# Power_Distribution.net
KiCad netlist of a schematic drawn in EAGLE
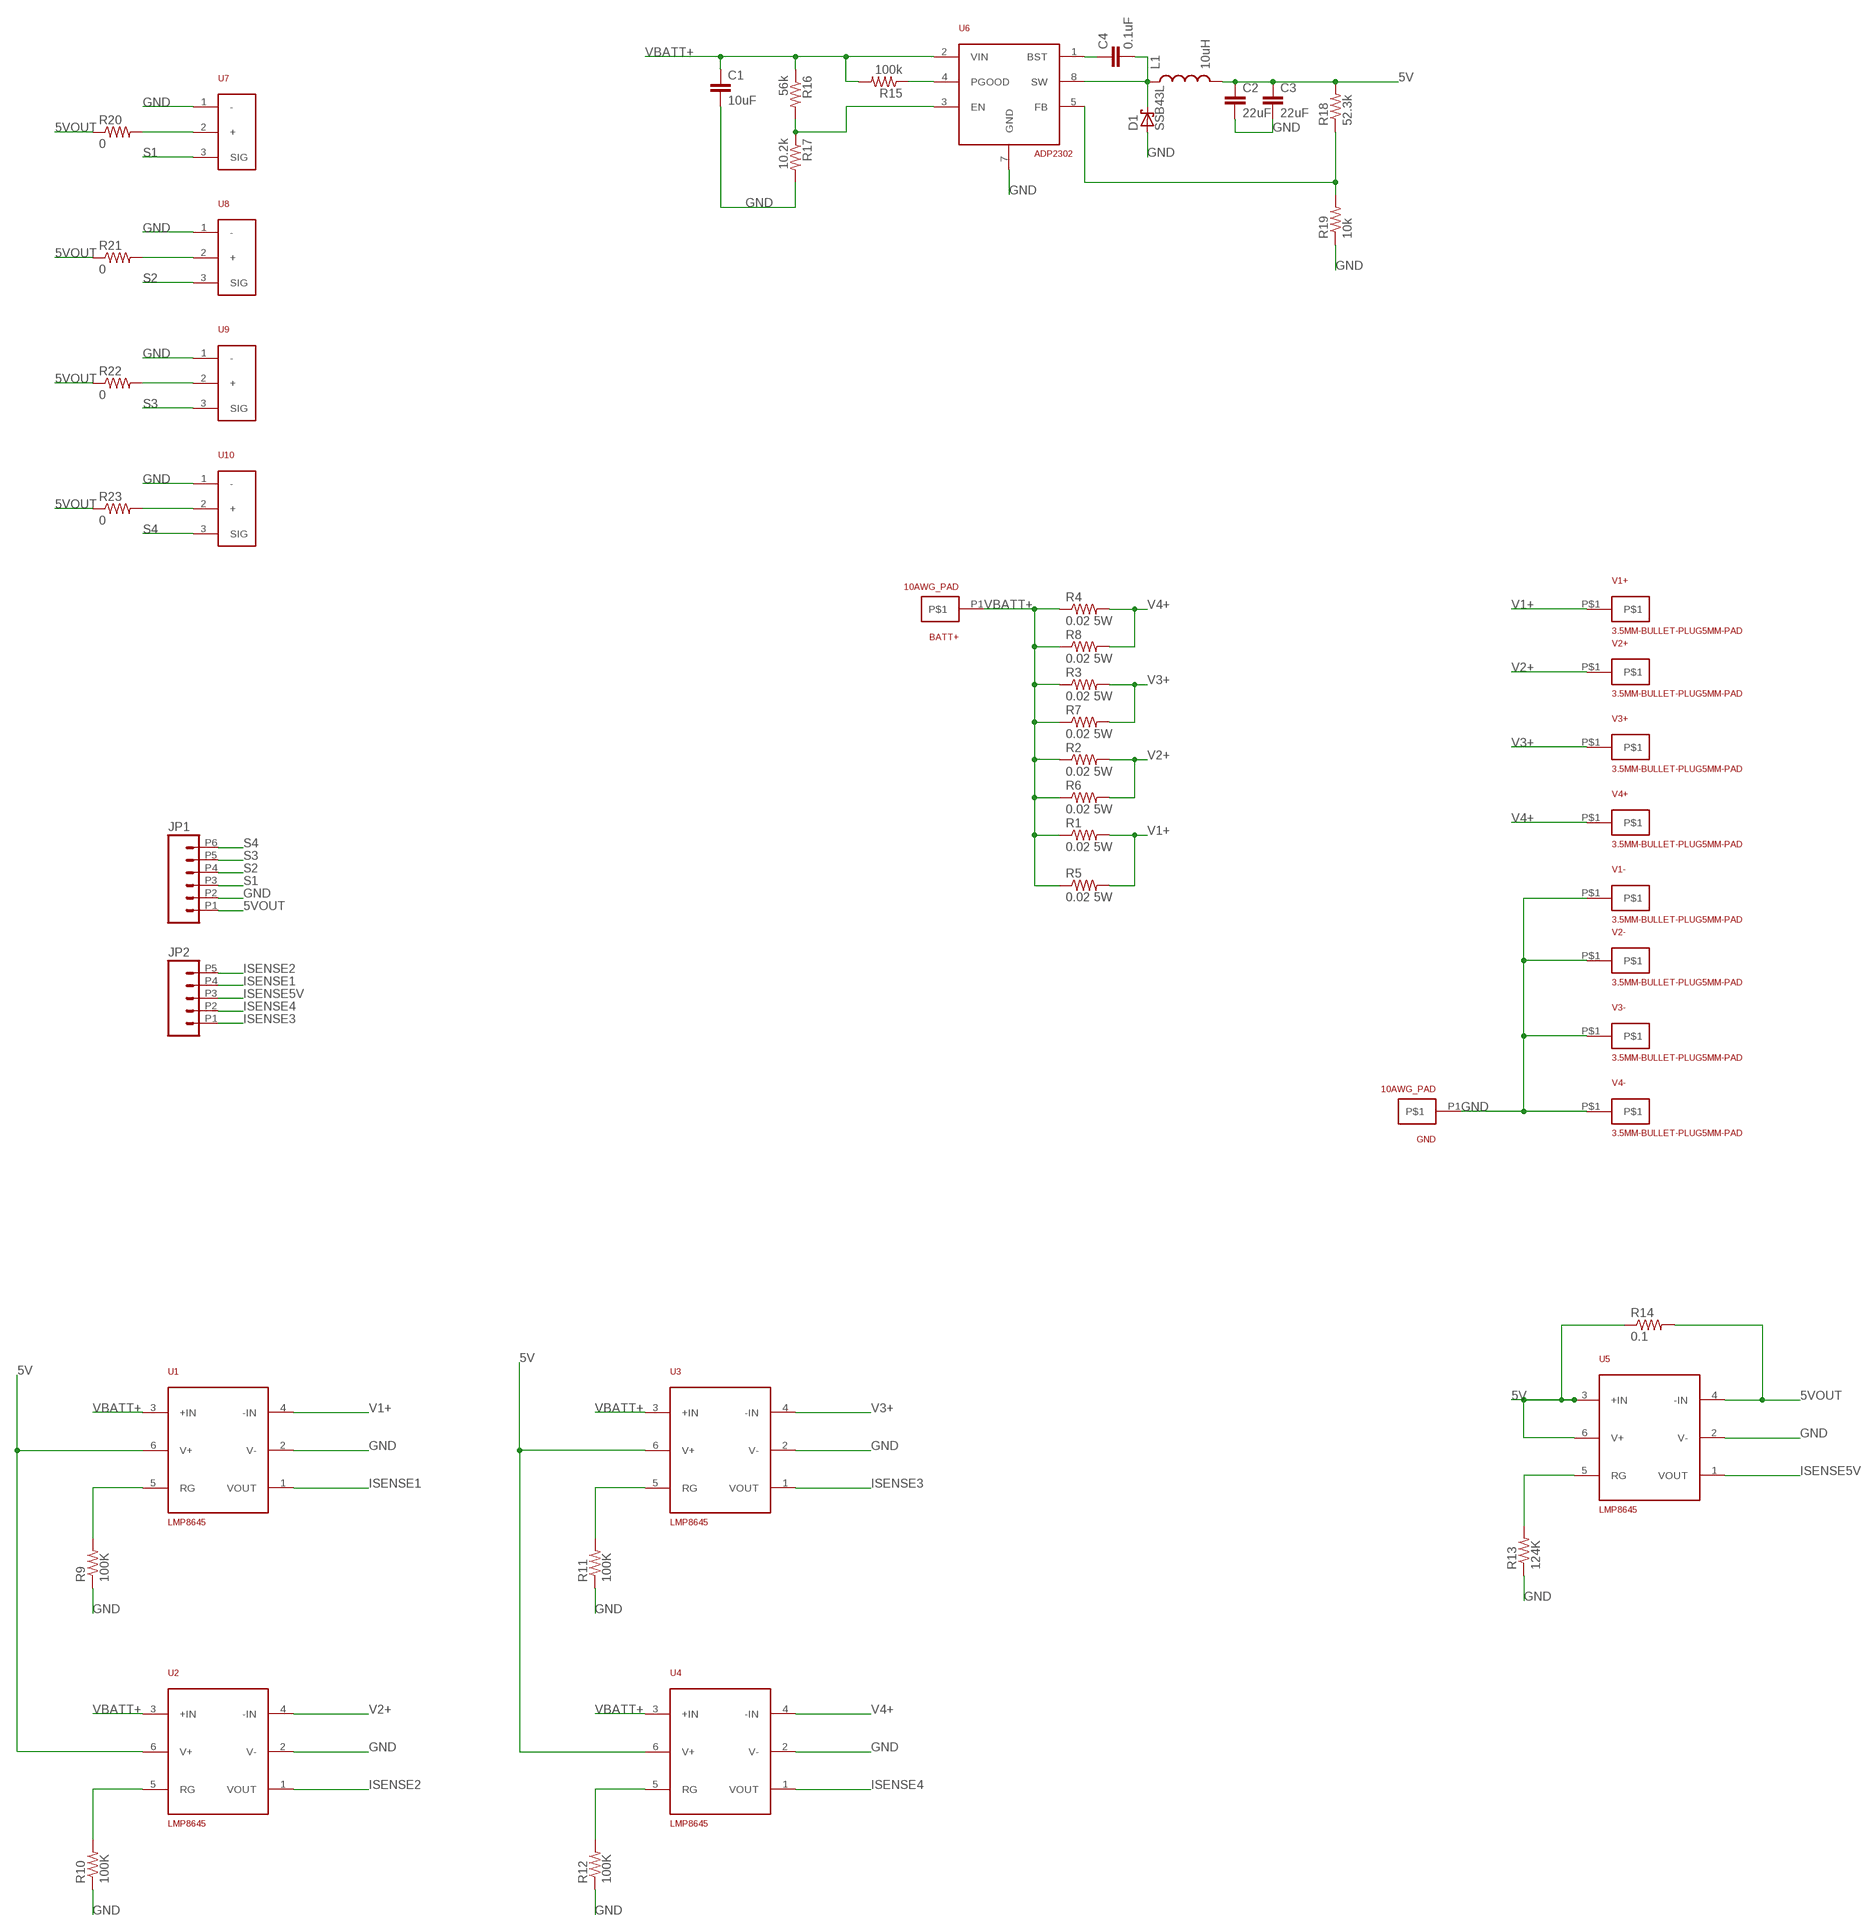
[diagram p0: schematic, sheet 1]

(export (version "E")
  (design (tool "Eeschema 10.0.6"))
  (components
    (comp (ref "BATT+")
      (value "10AWG_PAD")
      (footprint "eagle-import:10AWG_SOLDERPAD")
      (libsource (lib "eagle-import") (part "10AWG_PAD"))
    )
    (comp (ref "C1")
      (value "10uF")
      (footprint "eagle-import:0603-CAP")
      (libsource (lib "eagle-import") (part "CAP0603-CAP"))
    )
    (comp (ref "C2")
      (value "22uF")
      (footprint "eagle-import:0603-CAP")
      (libsource (lib "eagle-import") (part "CAP0603-CAP"))
    )
    (comp (ref "C3")
      (value "22uF")
      (footprint "eagle-import:0603-CAP")
      (libsource (lib "eagle-import") (part "CAP0603-CAP"))
    )
    (comp (ref "C4")
      (value "0.1uF")
      (footprint "eagle-import:0603-CAP")
      (libsource (lib "eagle-import") (part "CAP0603-CAP"))
    )
    (comp (ref "D1")
      (value "SSB43L")
      (footprint "eagle-import:SMB")
      (libsource (lib "eagle-import") (part "SCHOTTKY-DIODESMD"))
    )
    (comp (ref "GND")
      (value "10AWG_PAD")
      (footprint "eagle-import:10AWG_SOLDERPAD")
      (libsource (lib "eagle-import") (part "10AWG_PAD"))
    )
    (comp (ref "JP1")
      (value "M06DF13")
      (footprint "eagle-import:DF13A-6P-1.25H")
      (libsource (lib "eagle-import") (part "M06DF13"))
    )
    (comp (ref "JP2")
      (value "M05DF13")
      (footprint "eagle-import:DF13A-5P-1.25H")
      (libsource (lib "eagle-import") (part "M05DF13"))
    )
    (comp (ref "L1")
      (value "10uH")
      (footprint "eagle-import:0603")
      (libsource (lib "eagle-import") (part "INDUCTOR0603"))
    )
    (comp (ref "R1")
      (value "0.02 5W")
      (footprint "eagle-import:R2512")
      (libsource (lib "eagle-import") (part "RESISTOR2512"))
    )
    (comp (ref "R2")
      (value "0.02 5W")
      (footprint "eagle-import:R2512")
      (libsource (lib "eagle-import") (part "RESISTOR2512"))
    )
    (comp (ref "R3")
      (value "0.02 5W")
      (footprint "eagle-import:R2512")
      (libsource (lib "eagle-import") (part "RESISTOR2512"))
    )
    (comp (ref "R4")
      (value "0.02 5W")
      (footprint "eagle-import:R2512")
      (libsource (lib "eagle-import") (part "RESISTOR2512"))
    )
    (comp (ref "R5")
      (value "0.02 5W")
      (footprint "eagle-import:R2512")
      (libsource (lib "eagle-import") (part "RESISTOR2512"))
    )
    (comp (ref "R6")
      (value "0.02 5W")
      (footprint "eagle-import:R2512")
      (libsource (lib "eagle-import") (part "RESISTOR2512"))
    )
    (comp (ref "R7")
      (value "0.02 5W")
      (footprint "eagle-import:R2512")
      (libsource (lib "eagle-import") (part "RESISTOR2512"))
    )
    (comp (ref "R8")
      (value "0.02 5W")
      (footprint "eagle-import:R2512")
      (libsource (lib "eagle-import") (part "RESISTOR2512"))
    )
    (comp (ref "R9")
      (value "100K")
      (footprint "eagle-import:0603-RES")
      (libsource (lib "eagle-import") (part "RESISTOR0603-RES"))
    )
    (comp (ref "R10")
      (value "100K")
      (footprint "eagle-import:0603-RES")
      (libsource (lib "eagle-import") (part "RESISTOR0603-RES"))
    )
    (comp (ref "R11")
      (value "100K")
      (footprint "eagle-import:0603-RES")
      (libsource (lib "eagle-import") (part "RESISTOR0603-RES"))
    )
    (comp (ref "R12")
      (value "100K")
      (footprint "eagle-import:0603-RES")
      (libsource (lib "eagle-import") (part "RESISTOR0603-RES"))
    )
    (comp (ref "R13")
      (value "124K")
      (footprint "eagle-import:0603-RES")
      (libsource (lib "eagle-import") (part "RESISTOR0603-RES"))
    )
    (comp (ref "R14")
      (value "0.1")
      (footprint "eagle-import:0603-RES")
      (libsource (lib "eagle-import") (part "RESISTOR0603-RES"))
    )
    (comp (ref "R15")
      (value "100k")
      (footprint "eagle-import:0603-RES")
      (libsource (lib "eagle-import") (part "RESISTOR0603-RES"))
    )
    (comp (ref "R16")
      (value "56k")
      (footprint "eagle-import:0603-RES")
      (libsource (lib "eagle-import") (part "RESISTOR0603-RES"))
    )
    (comp (ref "R17")
      (value "10.2k")
      (footprint "eagle-import:0603-RES")
      (libsource (lib "eagle-import") (part "RESISTOR0603-RES"))
    )
    (comp (ref "R18")
      (value "52.3k")
      (footprint "eagle-import:0603-RES")
      (libsource (lib "eagle-import") (part "RESISTOR0603-RES"))
    )
    (comp (ref "R19")
      (value "10k")
      (footprint "eagle-import:0603-RES")
      (libsource (lib "eagle-import") (part "RESISTOR0603-RES"))
    )
    (comp (ref "R20")
      (value "0")
      (footprint "eagle-import:0603-RES")
      (libsource (lib "eagle-import") (part "RESISTOR0603-RES"))
    )
    (comp (ref "R21")
      (value "0")
      (footprint "eagle-import:0603-RES")
      (libsource (lib "eagle-import") (part "RESISTOR0603-RES"))
    )
    (comp (ref "R22")
      (value "0")
      (footprint "eagle-import:0603-RES")
      (libsource (lib "eagle-import") (part "RESISTOR0603-RES"))
    )
    (comp (ref "R23")
      (value "0")
      (footprint "eagle-import:0603-RES")
      (libsource (lib "eagle-import") (part "RESISTOR0603-RES"))
    )
    (comp (ref "U1")
      (value "LMP8645")
      (footprint "eagle-import:SOT23-6")
      (libsource (lib "eagle-import") (part "LMP8645"))
    )
    (comp (ref "U2")
      (value "LMP8645")
      (footprint "eagle-import:SOT23-6")
      (libsource (lib "eagle-import") (part "LMP8645"))
    )
    (comp (ref "U3")
      (value "LMP8645")
      (footprint "eagle-import:SOT23-6")
      (libsource (lib "eagle-import") (part "LMP8645"))
    )
    (comp (ref "U4")
      (value "LMP8645")
      (footprint "eagle-import:SOT23-6")
      (libsource (lib "eagle-import") (part "LMP8645"))
    )
    (comp (ref "U5")
      (value "LMP8645")
      (footprint "eagle-import:SOT23-6")
      (libsource (lib "eagle-import") (part "LMP8645"))
    )
    (comp (ref "U6")
      (value "ADP2302")
      (footprint "eagle-import:SOIC8")
      (libsource (lib "eagle-import") (part "ADP2302"))
    )
    (comp (ref "U7")
      (value "SERVOPLUGTHROUGHHOLE_0.1PITCH")
      (footprint "eagle-import:0.1-PITCH-3CONN_RANGLE")
      (libsource (lib "eagle-import") (part "SERVOPLUGTHROUGHHOLE_0.1PITCH"))
    )
    (comp (ref "U8")
      (value "SERVOPLUGTHROUGHHOLE_0.1PITCH")
      (footprint "eagle-import:0.1-PITCH-3CONN_RANGLE")
      (libsource (lib "eagle-import") (part "SERVOPLUGTHROUGHHOLE_0.1PITCH"))
    )
    (comp (ref "U9")
      (value "SERVOPLUGTHROUGHHOLE_0.1PITCH")
      (footprint "eagle-import:0.1-PITCH-3CONN_RANGLE")
      (libsource (lib "eagle-import") (part "SERVOPLUGTHROUGHHOLE_0.1PITCH"))
    )
    (comp (ref "U10")
      (value "SERVOPLUGTHROUGHHOLE_0.1PITCH")
      (footprint "eagle-import:0.1-PITCH-3CONN_RANGLE")
      (libsource (lib "eagle-import") (part "SERVOPLUGTHROUGHHOLE_0.1PITCH"))
    )
    (comp (ref "V1+")
      (value "3.5MM-BULLET-PLUG5MM-PAD")
      (footprint "eagle-import:5MMPLUG")
      (libsource (lib "eagle-import") (part "3.5MM-BULLET-PLUG5MM-PAD"))
    )
    (comp (ref "V1-")
      (value "3.5MM-BULLET-PLUG5MM-PAD")
      (footprint "eagle-import:5MMPLUG")
      (libsource (lib "eagle-import") (part "3.5MM-BULLET-PLUG5MM-PAD"))
    )
    (comp (ref "V2+")
      (value "3.5MM-BULLET-PLUG5MM-PAD")
      (footprint "eagle-import:5MMPLUG")
      (libsource (lib "eagle-import") (part "3.5MM-BULLET-PLUG5MM-PAD"))
    )
    (comp (ref "V2-")
      (value "3.5MM-BULLET-PLUG5MM-PAD")
      (footprint "eagle-import:5MMPLUG")
      (libsource (lib "eagle-import") (part "3.5MM-BULLET-PLUG5MM-PAD"))
    )
    (comp (ref "V3+")
      (value "3.5MM-BULLET-PLUG5MM-PAD")
      (footprint "eagle-import:5MMPLUG")
      (libsource (lib "eagle-import") (part "3.5MM-BULLET-PLUG5MM-PAD"))
    )
    (comp (ref "V3-")
      (value "3.5MM-BULLET-PLUG5MM-PAD")
      (footprint "eagle-import:5MMPLUG")
      (libsource (lib "eagle-import") (part "3.5MM-BULLET-PLUG5MM-PAD"))
    )
    (comp (ref "V4+")
      (value "3.5MM-BULLET-PLUG5MM-PAD")
      (footprint "eagle-import:5MMPLUG")
      (libsource (lib "eagle-import") (part "3.5MM-BULLET-PLUG5MM-PAD"))
    )
    (comp (ref "V4-")
      (value "3.5MM-BULLET-PLUG5MM-PAD")
      (footprint "eagle-import:5MMPLUG")
      (libsource (lib "eagle-import") (part "3.5MM-BULLET-PLUG5MM-PAD"))
    )
  )
  (nets
    (net (code "1") (name "/5V") (class "Default")
      (node (ref "C2") (pin "1") (pinfunction "1_1") (pintype "passive"))
      (node (ref "C3") (pin "1") (pinfunction "1_1") (pintype "passive"))
      (node (ref "L1") (pin "2") (pinfunction "2_2") (pintype "passive"))
      (node (ref "R14") (pin "1") (pinfunction "1_1") (pintype "passive"))
      (node (ref "R18") (pin "2") (pinfunction "2_2") (pintype "passive"))
      (node (ref "U1") (pin "6") (pinfunction "V+_6") (pintype "bidirectional"))
      (node (ref "U2") (pin "6") (pinfunction "V+_6") (pintype "bidirectional"))
      (node (ref "U3") (pin "6") (pinfunction "V+_6") (pintype "bidirectional"))
      (node (ref "U4") (pin "6") (pinfunction "V+_6") (pintype "bidirectional"))
      (node (ref "U5") (pin "3") (pinfunction "+IN_3") (pintype "bidirectional"))
      (node (ref "U5") (pin "6") (pinfunction "V+_6") (pintype "bidirectional"))
    )
    (net (code "2") (name "/5VOUT") (class "Default")
      (node (ref "JP1") (pin "P1") (pinfunction "1_P1") (pintype "passive"))
      (node (ref "R14") (pin "2") (pinfunction "2_2") (pintype "passive"))
      (node (ref "R20") (pin "1") (pinfunction "1_1") (pintype "passive"))
      (node (ref "R21") (pin "1") (pinfunction "1_1") (pintype "passive"))
      (node (ref "R22") (pin "1") (pinfunction "1_1") (pintype "passive"))
      (node (ref "R23") (pin "1") (pinfunction "1_1") (pintype "passive"))
      (node (ref "U5") (pin "4") (pinfunction "-IN_4") (pintype "bidirectional"))
    )
    (net (code "3") (name "/GND") (class "Default")
      (node (ref "C1") (pin "2") (pinfunction "2_2") (pintype "passive"))
      (node (ref "C2") (pin "2") (pinfunction "2_2") (pintype "passive"))
      (node (ref "C3") (pin "2") (pinfunction "2_2") (pintype "passive"))
      (node (ref "D1") (pin "A") (pinfunction "A_A") (pintype "passive"))
      (node (ref "GND") (pin "P1") (pinfunction "P$1_P1") (pintype "bidirectional"))
      (node (ref "JP1") (pin "P2") (pinfunction "2_P2") (pintype "passive"))
      (node (ref "R10") (pin "1") (pinfunction "1_1") (pintype "passive"))
      (node (ref "R11") (pin "1") (pinfunction "1_1") (pintype "passive"))
      (node (ref "R12") (pin "1") (pinfunction "1_1") (pintype "passive"))
      (node (ref "R13") (pin "1") (pinfunction "1_1") (pintype "passive"))
      (node (ref "R17") (pin "2") (pinfunction "2_2") (pintype "passive"))
      (node (ref "R19") (pin "1") (pinfunction "1_1") (pintype "passive"))
      (node (ref "R9") (pin "1") (pinfunction "1_1") (pintype "passive"))
      (node (ref "U1") (pin "2") (pinfunction "V-_2") (pintype "bidirectional"))
      (node (ref "U10") (pin "1") (pinfunction "-_1") (pintype "bidirectional"))
      (node (ref "U2") (pin "2") (pinfunction "V-_2") (pintype "bidirectional"))
      (node (ref "U3") (pin "2") (pinfunction "V-_2") (pintype "bidirectional"))
      (node (ref "U4") (pin "2") (pinfunction "V-_2") (pintype "bidirectional"))
      (node (ref "U5") (pin "2") (pinfunction "V-_2") (pintype "bidirectional"))
      (node (ref "U6") (pin "7") (pinfunction "GND_7") (pintype "bidirectional"))
      (node (ref "U7") (pin "1") (pinfunction "-_1") (pintype "bidirectional"))
      (node (ref "U8") (pin "1") (pinfunction "-_1") (pintype "bidirectional"))
      (node (ref "U9") (pin "1") (pinfunction "-_1") (pintype "bidirectional"))
      (node (ref "V1-") (pin "P$1") (pinfunction "P$1_P$1") (pintype "bidirectional"))
      (node (ref "V2-") (pin "P$1") (pinfunction "P$1_P$1") (pintype "bidirectional"))
      (node (ref "V3-") (pin "P$1") (pinfunction "P$1_P$1") (pintype "bidirectional"))
      (node (ref "V4-") (pin "P$1") (pinfunction "P$1_P$1") (pintype "bidirectional"))
    )
    (net (code "4") (name "/ISENSE1") (class "Default")
      (node (ref "JP2") (pin "P4") (pinfunction "4_P4") (pintype "passive"))
      (node (ref "U1") (pin "1") (pinfunction "VOUT_1") (pintype "bidirectional"))
    )
    (net (code "5") (name "/ISENSE2") (class "Default")
      (node (ref "JP2") (pin "P5") (pinfunction "5_P5") (pintype "passive"))
      (node (ref "U2") (pin "1") (pinfunction "VOUT_1") (pintype "bidirectional"))
    )
    (net (code "6") (name "/ISENSE3") (class "Default")
      (node (ref "JP2") (pin "P1") (pinfunction "1_P1") (pintype "passive"))
      (node (ref "U3") (pin "1") (pinfunction "VOUT_1") (pintype "bidirectional"))
    )
    (net (code "7") (name "/ISENSE4") (class "Default")
      (node (ref "JP2") (pin "P2") (pinfunction "2_P2") (pintype "passive"))
      (node (ref "U4") (pin "1") (pinfunction "VOUT_1") (pintype "bidirectional"))
    )
    (net (code "8") (name "/ISENSE5V") (class "Default")
      (node (ref "JP2") (pin "P3") (pinfunction "3_P3") (pintype "passive"))
      (node (ref "U5") (pin "1") (pinfunction "VOUT_1") (pintype "bidirectional"))
    )
    (net (code "9") (name "/S1") (class "Default")
      (node (ref "JP1") (pin "P3") (pinfunction "3_P3") (pintype "passive"))
      (node (ref "U7") (pin "3") (pinfunction "SIG_3") (pintype "bidirectional"))
    )
    (net (code "10") (name "/S2") (class "Default")
      (node (ref "JP1") (pin "P4") (pinfunction "4_P4") (pintype "passive"))
      (node (ref "U8") (pin "3") (pinfunction "SIG_3") (pintype "bidirectional"))
    )
    (net (code "11") (name "/S3") (class "Default")
      (node (ref "JP1") (pin "P5") (pinfunction "5_P5") (pintype "passive"))
      (node (ref "U9") (pin "3") (pinfunction "SIG_3") (pintype "bidirectional"))
    )
    (net (code "12") (name "/S4") (class "Default")
      (node (ref "JP1") (pin "P6") (pinfunction "6_P6") (pintype "passive"))
      (node (ref "U10") (pin "3") (pinfunction "SIG_3") (pintype "bidirectional"))
    )
    (net (code "13") (name "/V1+") (class "Default")
      (node (ref "R1") (pin "2") (pinfunction "2_2") (pintype "passive"))
      (node (ref "R5") (pin "2") (pinfunction "2_2") (pintype "passive"))
      (node (ref "U1") (pin "4") (pinfunction "-IN_4") (pintype "bidirectional"))
      (node (ref "V1+") (pin "P$1") (pinfunction "P$1_P$1") (pintype "bidirectional"))
    )
    (net (code "14") (name "/V2+") (class "Default")
      (node (ref "R2") (pin "2") (pinfunction "2_2") (pintype "passive"))
      (node (ref "R6") (pin "2") (pinfunction "2_2") (pintype "passive"))
      (node (ref "U2") (pin "4") (pinfunction "-IN_4") (pintype "bidirectional"))
      (node (ref "V2+") (pin "P$1") (pinfunction "P$1_P$1") (pintype "bidirectional"))
    )
    (net (code "15") (name "/V3+") (class "Default")
      (node (ref "R3") (pin "2") (pinfunction "2_2") (pintype "passive"))
      (node (ref "R7") (pin "2") (pinfunction "2_2") (pintype "passive"))
      (node (ref "U3") (pin "4") (pinfunction "-IN_4") (pintype "bidirectional"))
      (node (ref "V3+") (pin "P$1") (pinfunction "P$1_P$1") (pintype "bidirectional"))
    )
    (net (code "16") (name "/V4+") (class "Default")
      (node (ref "R4") (pin "2") (pinfunction "2_2") (pintype "passive"))
      (node (ref "R8") (pin "2") (pinfunction "2_2") (pintype "passive"))
      (node (ref "U4") (pin "4") (pinfunction "-IN_4") (pintype "bidirectional"))
      (node (ref "V4+") (pin "P$1") (pinfunction "P$1_P$1") (pintype "bidirectional"))
    )
    (net (code "17") (name "/VBATT+") (class "Default")
      (node (ref "BATT+") (pin "P1") (pinfunction "P$1_P1") (pintype "bidirectional"))
      (node (ref "C1") (pin "1") (pinfunction "1_1") (pintype "passive"))
      (node (ref "R1") (pin "1") (pinfunction "1_1") (pintype "passive"))
      (node (ref "R15") (pin "2") (pinfunction "2_2") (pintype "passive"))
      (node (ref "R16") (pin "1") (pinfunction "1_1") (pintype "passive"))
      (node (ref "R2") (pin "1") (pinfunction "1_1") (pintype "passive"))
      (node (ref "R3") (pin "1") (pinfunction "1_1") (pintype "passive"))
      (node (ref "R4") (pin "1") (pinfunction "1_1") (pintype "passive"))
      (node (ref "R5") (pin "1") (pinfunction "1_1") (pintype "passive"))
      (node (ref "R6") (pin "1") (pinfunction "1_1") (pintype "passive"))
      (node (ref "R7") (pin "1") (pinfunction "1_1") (pintype "passive"))
      (node (ref "R8") (pin "1") (pinfunction "1_1") (pintype "passive"))
      (node (ref "U1") (pin "3") (pinfunction "+IN_3") (pintype "bidirectional"))
      (node (ref "U2") (pin "3") (pinfunction "+IN_3") (pintype "bidirectional"))
      (node (ref "U3") (pin "3") (pinfunction "+IN_3") (pintype "bidirectional"))
      (node (ref "U4") (pin "3") (pinfunction "+IN_3") (pintype "bidirectional"))
      (node (ref "U6") (pin "2") (pinfunction "VIN_2") (pintype "bidirectional"))
    )
    (net (code "18") (name "Net-(U1-RG)") (class "Default")
      (node (ref "R9") (pin "2") (pinfunction "2_2") (pintype "passive"))
      (node (ref "U1") (pin "5") (pinfunction "RG_5") (pintype "bidirectional"))
    )
    (net (code "19") (name "Net-(U2-RG)") (class "Default")
      (node (ref "R10") (pin "2") (pinfunction "2_2") (pintype "passive"))
      (node (ref "U2") (pin "5") (pinfunction "RG_5") (pintype "bidirectional"))
    )
    (net (code "20") (name "Net-(U3-RG)") (class "Default")
      (node (ref "R11") (pin "2") (pinfunction "2_2") (pintype "passive"))
      (node (ref "U3") (pin "5") (pinfunction "RG_5") (pintype "bidirectional"))
    )
    (net (code "21") (name "Net-(U4-RG)") (class "Default")
      (node (ref "R12") (pin "2") (pinfunction "2_2") (pintype "passive"))
      (node (ref "U4") (pin "5") (pinfunction "RG_5") (pintype "bidirectional"))
    )
    (net (code "22") (name "Net-(U5-RG)") (class "Default")
      (node (ref "R13") (pin "2") (pinfunction "2_2") (pintype "passive"))
      (node (ref "U5") (pin "5") (pinfunction "RG_5") (pintype "bidirectional"))
    )
    (net (code "23") (name "Net-(U6-BST)") (class "Default")
      (node (ref "C4") (pin "1") (pinfunction "1_1") (pintype "passive"))
      (node (ref "U6") (pin "1") (pinfunction "BST_1") (pintype "bidirectional"))
    )
    (net (code "24") (name "Net-(U6-EN)") (class "Default")
      (node (ref "R16") (pin "2") (pinfunction "2_2") (pintype "passive"))
      (node (ref "R17") (pin "1") (pinfunction "1_1") (pintype "passive"))
      (node (ref "U6") (pin "3") (pinfunction "EN_3") (pintype "bidirectional"))
    )
    (net (code "25") (name "Net-(U6-FB)") (class "Default")
      (node (ref "R18") (pin "1") (pinfunction "1_1") (pintype "passive"))
      (node (ref "R19") (pin "2") (pinfunction "2_2") (pintype "passive"))
      (node (ref "U6") (pin "5") (pinfunction "FB_5") (pintype "bidirectional"))
    )
    (net (code "26") (name "Net-(U6-PGOOD)") (class "Default")
      (node (ref "R15") (pin "1") (pinfunction "1_1") (pintype "passive"))
      (node (ref "U6") (pin "4") (pinfunction "PGOOD_4") (pintype "bidirectional"))
    )
    (net (code "27") (name "Net-(U6-SW)") (class "Default")
      (node (ref "C4") (pin "2") (pinfunction "2_2") (pintype "passive"))
      (node (ref "D1") (pin "C") (pinfunction "C_C") (pintype "passive"))
      (node (ref "L1") (pin "1") (pinfunction "1_1") (pintype "passive"))
      (node (ref "U6") (pin "8") (pinfunction "SW_8") (pintype "bidirectional"))
    )
    (net (code "28") (name "Net-(U7-+)") (class "Default")
      (node (ref "R20") (pin "2") (pinfunction "2_2") (pintype "passive"))
      (node (ref "U7") (pin "2") (pinfunction "+_2") (pintype "bidirectional"))
    )
    (net (code "29") (name "Net-(U8-+)") (class "Default")
      (node (ref "R21") (pin "2") (pinfunction "2_2") (pintype "passive"))
      (node (ref "U8") (pin "2") (pinfunction "+_2") (pintype "bidirectional"))
    )
    (net (code "30") (name "Net-(U9-+)") (class "Default")
      (node (ref "R22") (pin "2") (pinfunction "2_2") (pintype "passive"))
      (node (ref "U9") (pin "2") (pinfunction "+_2") (pintype "bidirectional"))
    )
    (net (code "31") (name "Net-(U10-+)") (class "Default")
      (node (ref "R23") (pin "2") (pinfunction "2_2") (pintype "passive"))
      (node (ref "U10") (pin "2") (pinfunction "+_2") (pintype "bidirectional"))
    )
  )
)
